# 2_Battery_Monitoring_And_Switches.net
KiCad netlist of a schematic drawn in Altium Designer
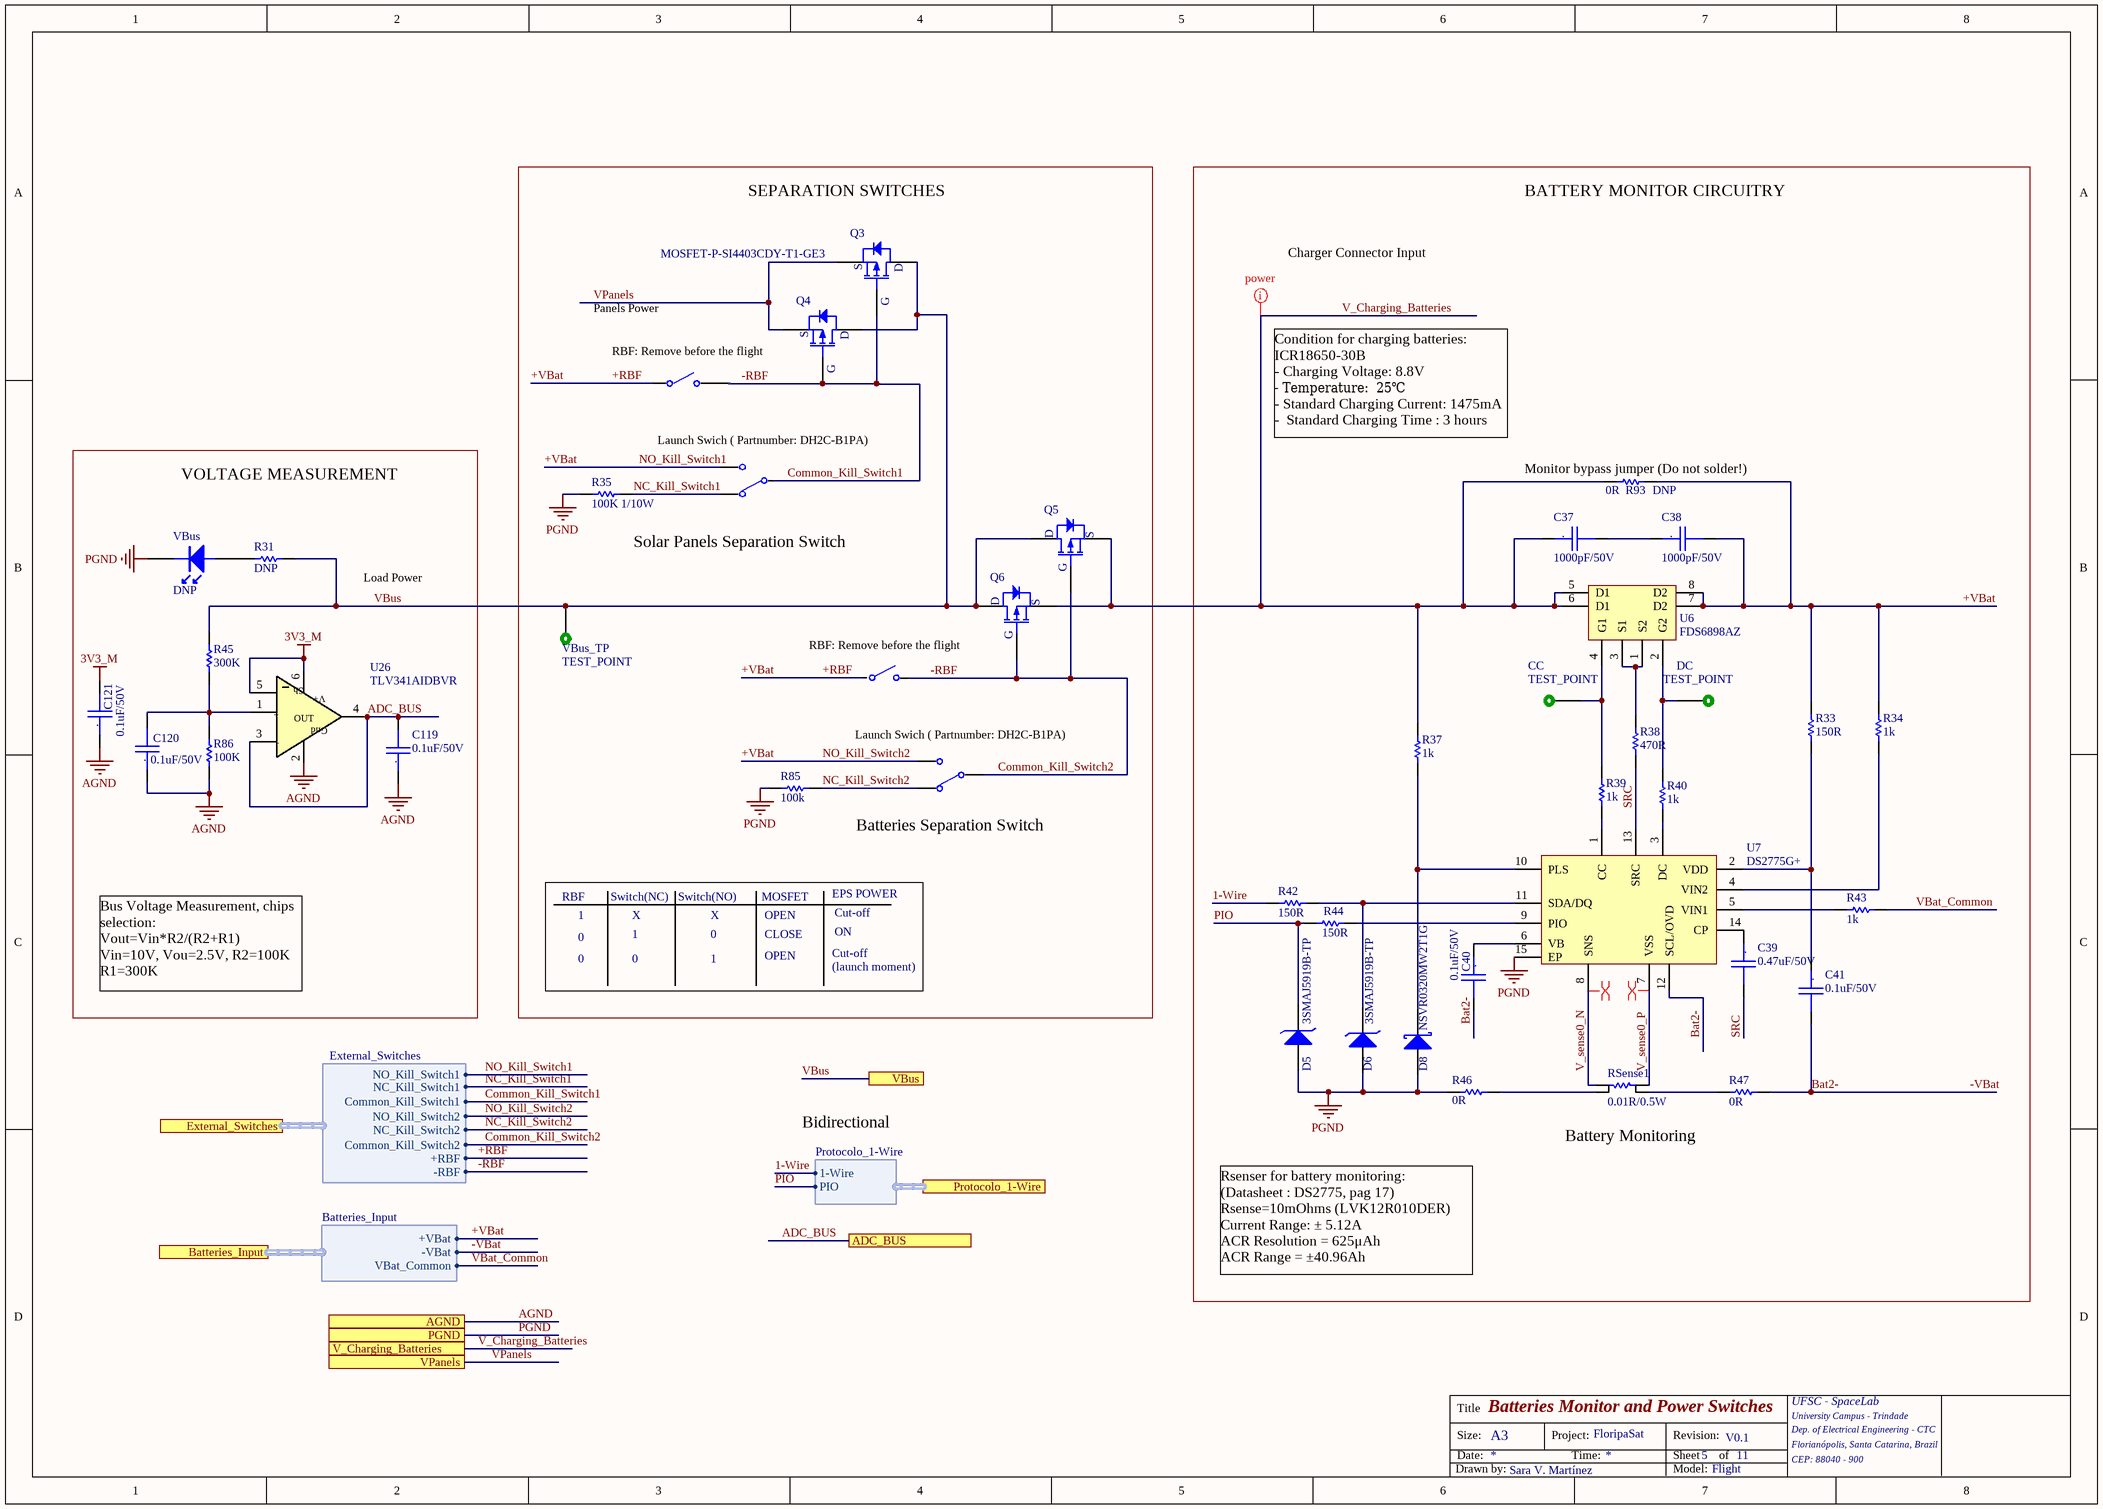
[diagram p0: 2_Battery_Monitoring_And_Switches.SchDoc]

(export (version "E")
  (design (tool "Eeschema 10.0.6"))
  (components
    (comp (ref "C37")
      (value "1000pF/50V")
      (footprint "CC0603")
      (description "CAP CER 1000pF 50V 10% X7R 0603")
      (fields (field (name "PARTNUMBER") "GRM188R71H102KA01D"))
      (libsource (lib "Floripasat_lib") (part "Cap_Cer_X7R_1000pF_50V_0603"))
    )
    (comp (ref "C38")
      (value "1000pF/50V")
      (footprint "CC0603")
      (description "CAP CER 1000pF 50V 10% X7R 0603")
      (fields (field (name "PARTNUMBER") "GRM188R71H102KA01D"))
      (libsource (lib "Floripasat_lib") (part "Cap_Cer_X7R_1000pF_50V_0603"))
    )
    (comp (ref "C39")
      (value "0.47uF/50V")
      (footprint "CC0603")
      (description "CAP CER 0.47UF 50V 10% X7R 0603")
      (fields (field (name "PARTNUMBER") "C1608X7R1H474K080AE"))
      (libsource (lib "FloripaSatSchlib") (part "Cap_Cer_X7R_0.47uF_50V_0603"))
    )
    (comp (ref "C40")
      (value "0.1uF/50V")
      (footprint "CC0603")
      (description "CAP CER 0.1UF 50V 10% X7R 0603")
      (fields (field (name "PARTNUMBER") "GRM188R71H104KA93D"))
      (libsource (lib "FloripaSatSchlib") (part "Cap_Cer_X7R_0.1uF_50V_0603"))
    )
    (comp (ref "C41")
      (value "0.1uF/50V")
      (footprint "CC0603")
      (description "CAP CER 0.1UF 50V 10% X7R 0603")
      (fields (field (name "PARTNUMBER") "GRM188R71H104KA93D"))
      (libsource (lib "FloripaSatSchlib") (part "Cap_Cer_X7R_0.1uF_50V_0603"))
    )
    (comp (ref "C119")
      (value "0.1uF/50V")
      (footprint "CC0603")
      (description "CAP CER 0.1UF 50V 10% X7R 0603")
      (fields (field (name "PARTNUMBER") "GRM188R71H104KA93D"))
      (libsource (lib "FloripaSatSchlib") (part "Cap_Cer_X7R_0.1uF_50V_0603"))
    )
    (comp (ref "C120")
      (value "0.1uF/50V")
      (footprint "CC0603")
      (description "CAP CER 0.1UF 50V 10% X7R 0603")
      (fields (field (name "PARTNUMBER") "GRM188R71H104KA93D"))
      (libsource (lib "FloripaSatSchlib") (part "Cap_Cer_X7R_0.1uF_50V_0603"))
    )
    (comp (ref "C121")
      (value "0.1uF/50V")
      (footprint "CC0603")
      (description "CAP CER 0.1UF 50V 10% X7R 0603")
      (fields (field (name "PARTNUMBER") "GRM188R71H104KA93D"))
      (libsource (lib "FloripaSatSchlib") (part "Cap_Cer_X7R_0.1uF_50V_0603"))
    )
    (comp (ref "CC")
      (value "TEST_POINT")
      (footprint "TEST_POINT")
      (description "Test point")
      (libsource (lib "Floripasat_lib") (part "TEST_POINT"))
    )
    (comp (ref "D5")
      (value "3SMAJ5919B-TP")
      (footprint "DO-214AC")
      (description "DIODE ZENER 5.6V 3W DO214AC")
      (libsource (lib "Floripasat_lib") (part "DIODE_ZENER_5.6V_3SMAJ5919B"))
    )
    (comp (ref "D6")
      (value "3SMAJ5919B-TP")
      (footprint "DO-214AC")
      (description "DIODE ZENER 5.6V 3W DO214AC")
      (libsource (lib "Floripasat_lib") (part "DIODE_ZENER_5.6V_3SMAJ5919B"))
    )
    (comp (ref "D8")
      (value "NSVR0320MW2T1G")
      (footprint "SOD323F")
      (description "DIODE SCHOTTKY 23V 1A SOD323F")
      (libsource (lib "FloripaSatSchlib") (part "DIODE_SCHOTTKY_23V_1A_NSVR0320MW2T1G"))
    )
    (comp (ref "DC")
      (value "TEST_POINT")
      (footprint "TEST_POINT")
      (description "Test point")
      (libsource (lib "Floripasat_lib") (part "TEST_POINT"))
    )
    (comp (ref "Q3")
      (value "MOSFET-P-SI4403CDY-T1-GE3")
      (footprint "SOIC8_Mosfet")
      (description "MOSFET 1.8V P-Channel 20 V, 0.0155 Ω typ., 13.4 A")
      (fields (field (name "PARTNUMBER") "SI4403CDY-T1-GE3") (field (name "PUBLISHER") "Altium Limited"))
      (libsource (lib "FloripaSatSchlib") (part "MOSFET-P- SI4403CDY-T1-GE3"))
    )
    (comp (ref "Q4")
      (value "MOSFET-P-SI4403CDY-T1-GE3")
      (footprint "SOIC8_Mosfet")
      (description "MOSFET 1.8V P-Channel 20 V, 0.0155 Ω typ., 13.4 A")
      (fields (field (name "PARTNUMBER") "SI4403CDY-T1-GE3") (field (name "PUBLISHER") "Altium Limited"))
      (libsource (lib "FloripaSatSchlib") (part "MOSFET-P- SI4403CDY-T1-GE3"))
    )
    (comp (ref "Q5")
      (value "MOSFET-P-SI4403CDY-T1-GE3")
      (footprint "SOIC8_Mosfet")
      (description "MOSFET 1.8V P-Channel 20 V, 0.0155 Ω typ., 13.4 A")
      (fields (field (name "PARTNUMBER") "SI4403CDY-T1-GE3") (field (name "PUBLISHER") "Altium Limited"))
      (libsource (lib "FloripaSatSchlib") (part "MOSFET-P- SI4403CDY-T1-GE3"))
    )
    (comp (ref "Q6")
      (value "MOSFET-P-SI4403CDY-T1-GE3")
      (footprint "SOIC8_Mosfet")
      (description "MOSFET 1.8V P-Channel 20 V, 0.0155 Ω typ., 13.4 A")
      (fields (field (name "PARTNUMBER") "SI4403CDY-T1-GE3") (field (name "PUBLISHER") "Altium Limited"))
      (libsource (lib "FloripaSatSchlib") (part "MOSFET-P- SI4403CDY-T1-GE3"))
    )
    (comp (ref "R31")
      (value "DNP")
      (footprint "0603")
      (description "RES 1.0K OHM 1/8W 1% 0603")
      (fields (field (name "PARTNUMBER") "MCT06030C1001FP500"))
      (libsource (lib "FloripaSatSchlib") (part "R1.0k_1%_1/8W_0603"))
    )
    (comp (ref "R33")
      (value "150R")
      (footprint "0603")
      (description "RES 150R OHM 1/8W 1% 0603")
      (fields (field (name "PARTNUMBER") "CRCW0603150RFKEA"))
      (libsource (lib "FloripaSatSchlib") (part "R150R_1%_1/8W_0603"))
    )
    (comp (ref "R34")
      (value "1k")
      (footprint "0603")
      (description "RES 1.0K OHM 1/8W 1% 0603")
      (fields (field (name "PARTNUMBER") "MCT06030C1001FP500"))
      (libsource (lib "FloripaSatSchlib") (part "R1.0k_1%_1/8W_0603"))
    )
    (comp (ref "R35")
      (value "100K 1/10W")
      (footprint "0805")
      (description "RES 100K OHM 1/10W 0.1% 0805")
      (fields (field (name "PARTNUMBER") "CPF-A-0805B100KE"))
      (libsource (lib "FloripaSatSchlib") (part "R100R_0.1%_1/10W_0805"))
    )
    (comp (ref "R37")
      (value "1k")
      (footprint "0603")
      (description "RES 1.0K OHM 1/8W 1% 0603")
      (fields (field (name "PARTNUMBER") "MCT06030C1001FP500"))
      (libsource (lib "FloripaSatSchlib") (part "R1.0k_1%_1/8W_0603"))
    )
    (comp (ref "R38")
      (value "470R")
      (footprint "0603")
      (description "RES 470R OHM 1/8W 1% 0603")
      (fields (field (name "PARTNUMBER") "MCT06030C4700FP500"))
      (libsource (lib "FloripaSatSchlib") (part "R470R_1%_1/8W_0603"))
    )
    (comp (ref "R39")
      (value "1k")
      (footprint "0603")
      (description "RES 1.0K OHM 1/8W 1% 0603")
      (fields (field (name "PARTNUMBER") "MCT06030C1001FP500"))
      (libsource (lib "FloripaSatSchlib") (part "R1.0k_1%_1/8W_0603"))
    )
    (comp (ref "R40")
      (value "1k")
      (footprint "0603")
      (description "RES 1.0K OHM 1/8W 1% 0603")
      (fields (field (name "PARTNUMBER") "MCT06030C1001FP500"))
      (libsource (lib "FloripaSatSchlib") (part "R1.0k_1%_1/8W_0603"))
    )
    (comp (ref "R42")
      (value "150R")
      (footprint "0603")
      (description "RES 150R OHM 1/8W 1% 0603")
      (fields (field (name "PARTNUMBER") "CRCW0603150RFKEA"))
      (libsource (lib "FloripaSatSchlib") (part "R150R_1%_1/8W_0603"))
    )
    (comp (ref "R43")
      (value "1k")
      (footprint "0603")
      (description "RES 1.0K OHM 1/8W 1% 0603")
      (fields (field (name "PARTNUMBER") "MCT06030C1001FP500"))
      (libsource (lib "FloripaSatSchlib") (part "R1.0k_1%_1/8W_0603"))
    )
    (comp (ref "R44")
      (value "150R")
      (footprint "0603")
      (description "RES 150R OHM 1/8W 1% 0603")
      (fields (field (name "PARTNUMBER") "CRCW0603150RFKEA"))
      (libsource (lib "FloripaSatSchlib") (part "R150R_1%_1/8W_0603"))
    )
    (comp (ref "R45")
      (value "300K")
      (footprint "0603")
      (description "RES 300K OHM 1/10W 0.1% 0603")
      (fields (field (name "PARTNUMBER") "RG1608P-304-B-T5"))
      (libsource (lib "FloripaSatSchlib") (part "R300K_0.1%_1/10W_0603"))
    )
    (comp (ref "R46")
      (value "0R")
      (footprint "1206")
      (description "RES 0.0 OHM 1/2W JUMP 1206")
      (fields (field (name "PARTNUMBER") "CRCW12060000Z0EAHP"))
      (libsource (lib "FloripaSatSchlib") (part "R0R_JUMPER_1/2W_1206"))
    )
    (comp (ref "R47")
      (value "0R")
      (footprint "1206")
      (description "RES 0.0 OHM 1/2W JUMP 1206")
      (fields (field (name "PARTNUMBER") "CRCW12060000Z0EAHP"))
      (libsource (lib "FloripaSatSchlib") (part "R0R_JUMPER_1/2W_1206"))
    )
    (comp (ref "R85")
      (value "100k")
      (footprint "0805")
      (description "RES 100k OHM 1/8W 1% 0805")
      (fields (field (name "PARTNUMBER") "CPF-A-0805B100KE"))
      (libsource (lib "FloripaSatSchlib") (part "R1.0k_1%_1/8W_0805"))
    )
    (comp (ref "R86")
      (value "100K")
      (footprint "0603")
      (description "RES 100K OHM 1/10W 1% 0603")
      (fields (field (name "PARTNUMBER") "CRCW0603100KFKEA"))
      (libsource (lib "FloripaSatSchlib") (part "R100K_1%_1/10W_0603"))
    )
    (comp (ref "R93")
      (value "0R")
      (footprint "1206")
      (description "RES 0.0 OHM 1/2W JUMP 1206")
      (fields (field (name "PARTNUMBER") "CRCW12060000Z0EAHP"))
      (libsource (lib "FloripaSatSchlib") (part "R0R_JUMPER_1/2W_1206"))
    )
    (comp (ref "RSense1")
      (value "0.01R/0.5W")
      (footprint "1206 - ohmite")
      (description "Current Sense Resistors - SMD 0.01ohm .5% 4 Terminal")
      (fields (field (name "PARTNUMBER") "LVK12R010DER"))
      (libsource (lib "FloripaSatSchlib") (part "R0.01R_0.5%_0.5W_1206_4_terminal"))
    )
    (comp (ref "U6")
      (value "FDS6898AZ")
      (footprint "SOIC8")
      (description "MOSFET 2N-CH 20V 9.4A 8SOIC")
      (libsource (lib "FloripaSatSchlib") (part "FDS6898AZ"))
    )
    (comp (ref "U7")
      (value "DS2775G+")
      (footprint "TDFN-14-EP_3x5")
      (description "IC FUEL GAUGE LI+ 2CELL 14-TDFN")
      (libsource (lib "FloripaSatSchlib") (part "DS2775G+"))
    )
    (comp (ref "U26")
      (value "TLV341AIDBVR")
      (footprint "SOT-23 6L")
      (libsource (lib "componentes_6_11") (part "TLV341AIDBVR"))
    )
    (comp (ref "VBus")
      (value "DNP")
      (footprint "0603-LED")
      (description "SMD Green LED")
      (fields (field (name "PARTNUMBER") "150060VS75000"))
      (libsource (lib "FloripaSatSchlib") (part "LED/G_0603"))
    )
    (comp (ref "VBus_TP")
      (value "TEST_POINT")
      (footprint "TEST_POINT")
      (description "Test point")
      (libsource (lib "Floripasat_lib") (part "TEST_POINT"))
    )
  )
  (nets
    (net (code "4") (name "/+RBF") (class "Default")
      (node (ref "C38") (pin "2") (pinfunction "2_2") (pintype "passive"))
      (node (ref "R33") (pin "1") (pinfunction "1_1") (pintype "passive"))
      (node (ref "R34") (pin "2") (pinfunction "2_2") (pintype "passive"))
      (node (ref "R93") (pin "2") (pinfunction "2_2") (pintype "passive"))
      (node (ref "U6") (pin "7") (pinfunction "D2_7") (pintype "passive"))
      (node (ref "U6") (pin "8") (pinfunction "D2_8") (pintype "passive"))
    )
    (net (code "5") (name "/-RBF") (class "Default")
      (node (ref "Q3") (pin "2") (pinfunction "G_2") (pintype "passive"))
      (node (ref "Q4") (pin "2") (pinfunction "G_2") (pintype "passive"))
      (node (ref "Q5") (pin "2") (pinfunction "G_2") (pintype "passive"))
      (node (ref "Q6") (pin "2") (pinfunction "G_2") (pintype "passive"))
    )
    (net (code "6") (name "/-VBat") (class "Default")
      (node (ref "C40") (pin "2") (pinfunction "2_2") (pintype "passive"))
      (node (ref "C41") (pin "2") (pinfunction "2_2") (pintype "passive"))
      (node (ref "R47") (pin "1") (pinfunction "1_1") (pintype "passive"))
      (node (ref "U7") (pin "12") (pinfunction "SCL/OVD_12") (pintype "passive"))
    )
    (net (code "7") (name "/1-Wire") (class "Default")
      (node (ref "R42") (pin "2") (pinfunction "2_2") (pintype "passive"))
    )
    (net (code "8") (name "/ADC_BUS") (class "Default")
      (node (ref "C119") (pin "2") (pinfunction "2_2") (pintype "passive"))
      (node (ref "U26") (pin "3") (pinfunction "-IN_3") (pintype "passive"))
      (node (ref "U26") (pin "4") (pinfunction "OUT_4") (pintype "passive"))
    )
    (net (code "9") (name "/NC_Kill_Switch1") (class "Default")
      (node (ref "R35") (pin "2") (pinfunction "2_2") (pintype "passive"))
    )
    (net (code "10") (name "/NC_Kill_Switch2") (class "Default")
      (node (ref "R85") (pin "2") (pinfunction "2_2") (pintype "passive"))
    )
    (net (code "11") (name "/PIO") (class "Default")
      (node (ref "D5") (pin "1") (pinfunction "K_1") (pintype "passive"))
      (node (ref "R44") (pin "2") (pinfunction "2_2") (pintype "passive"))
    )
    (net (code "12") (name "/SRC") (class "Default")
      (node (ref "C39") (pin "2") (pinfunction "2_2") (pintype "passive"))
      (node (ref "R38") (pin "1") (pinfunction "1_1") (pintype "passive"))
      (node (ref "U7") (pin "13") (pinfunction "SRC_13") (pintype "passive"))
    )
    (net (code "13") (name "/VBat_Common") (class "Default")
      (node (ref "R43") (pin "1") (pinfunction "1_1") (pintype "passive"))
    )
    (net (code "14") (name "/VBus") (class "Default")
      (node (ref "Q3") (pin "3") (pinfunction "D_3") (pintype "passive"))
      (node (ref "Q4") (pin "3") (pinfunction "D_3") (pintype "passive"))
      (node (ref "Q5") (pin "3") (pinfunction "D_3") (pintype "passive"))
      (node (ref "Q6") (pin "3") (pinfunction "D_3") (pintype "passive"))
      (node (ref "R31") (pin "1") (pinfunction "1_1") (pintype "passive"))
      (node (ref "R45") (pin "2") (pinfunction "2_2") (pintype "passive"))
      (node (ref "VBus_TP") (pin "1") (pinfunction "1_1") (pintype "passive"))
    )
    (net (code "15") (name "/VPanels") (class "Default")
      (node (ref "Q3") (pin "1") (pinfunction "S_1") (pintype "passive"))
      (node (ref "Q4") (pin "1") (pinfunction "S_1") (pintype "passive"))
    )
    (net (code "16") (name "/V_Charging_Batteries") (class "Default")
      (node (ref "C37") (pin "1") (pinfunction "1_1") (pintype "passive"))
      (node (ref "Q5") (pin "1") (pinfunction "S_1") (pintype "passive"))
      (node (ref "Q6") (pin "1") (pinfunction "S_1") (pintype "passive"))
      (node (ref "R37") (pin "2") (pinfunction "2_2") (pintype "passive"))
      (node (ref "R93") (pin "1") (pinfunction "1_1") (pintype "passive"))
      (node (ref "U6") (pin "5") (pinfunction "D1_5") (pintype "passive"))
      (node (ref "U6") (pin "6") (pinfunction "D1_6") (pintype "passive"))
    )
    (net (code "17") (name "/V_sense0_N") (class "Default")
      (node (ref "RSense1") (pin "2") (pinfunction "2_2") (pintype "passive"))
      (node (ref "U7") (pin "8") (pinfunction "SNS_8") (pintype "passive"))
    )
    (net (code "18") (name "/V_sense0_P") (class "Default")
      (node (ref "RSense1") (pin "1") (pinfunction "1_1") (pintype "passive"))
      (node (ref "U7") (pin "7") (pinfunction "VSS_7") (pintype "passive"))
    )
    (net (code "22") (name "3V3_M") (class "Default")
      (node (ref "C121") (pin "2") (pinfunction "2_2") (pintype "passive"))
      (node (ref "U26") (pin "5") (pinfunction "EN_5") (pintype "passive"))
      (node (ref "U26") (pin "6") (pinfunction "V+_6") (pintype "passive"))
    )
    (net (code "23") (name "AGND") (class "Default")
      (node (ref "C119") (pin "1") (pinfunction "1_1") (pintype "passive"))
      (node (ref "C120") (pin "1") (pinfunction "1_1") (pintype "passive"))
      (node (ref "C121") (pin "1") (pinfunction "1_1") (pintype "passive"))
      (node (ref "R86") (pin "1") (pinfunction "1_1") (pintype "passive"))
      (node (ref "U26") (pin "2") (pinfunction "Gnd_2") (pintype "passive"))
    )
    (net (code "24") (name "Net-(C37-Pad2)") (class "Default")
      (node (ref "C37") (pin "2") (pinfunction "2_2") (pintype "passive"))
      (node (ref "C38") (pin "1") (pinfunction "1_1") (pintype "passive"))
    )
    (net (code "25") (name "Net-(D6-K)") (class "Default")
      (node (ref "D6") (pin "1") (pinfunction "K_1") (pintype "passive"))
      (node (ref "R42") (pin "1") (pinfunction "1_1") (pintype "passive"))
      (node (ref "U7") (pin "11") (pinfunction "SDA/DQ_11") (pintype "passive"))
    )
    (net (code "26") (name "Net-(D8-K)") (class "Default")
      (node (ref "D8") (pin "1") (pinfunction "K_1") (pintype "passive"))
      (node (ref "R37") (pin "1") (pinfunction "1_1") (pintype "passive"))
      (node (ref "U7") (pin "10") (pinfunction "PLS_10") (pintype "passive"))
    )
    (net (code "27") (name "Net-(R46-Pad1)") (class "Default")
      (node (ref "R46") (pin "1") (pinfunction "1_1") (pintype "passive"))
      (node (ref "RSense1") (pin "4") (pinfunction "4_4") (pintype "passive"))
    )
    (net (code "28") (name "Net-(R47-Pad2)") (class "Default")
      (node (ref "R47") (pin "2") (pinfunction "2_2") (pintype "passive"))
      (node (ref "RSense1") (pin "3") (pinfunction "3_3") (pintype "passive"))
    )
    (net (code "29") (name "Net-(U6-G1)") (class "Default")
      (node (ref "CC") (pin "1") (pinfunction "1_1") (pintype "passive"))
      (node (ref "R39") (pin "2") (pinfunction "2_2") (pintype "passive"))
      (node (ref "U6") (pin "4") (pinfunction "G1_4") (pintype "passive"))
    )
    (net (code "30") (name "Net-(U6-G2)") (class "Default")
      (node (ref "DC") (pin "1") (pinfunction "1_1") (pintype "passive"))
      (node (ref "R40") (pin "2") (pinfunction "2_2") (pintype "passive"))
      (node (ref "U6") (pin "2") (pinfunction "G2_2") (pintype "passive"))
    )
    (net (code "31") (name "Net-(U6-S1)") (class "Default")
      (node (ref "R38") (pin "2") (pinfunction "2_2") (pintype "passive"))
      (node (ref "U6") (pin "1") (pinfunction "S2_1") (pintype "passive"))
      (node (ref "U6") (pin "3") (pinfunction "S1_3") (pintype "passive"))
    )
    (net (code "32") (name "Net-(U7-CC)") (class "Default")
      (node (ref "R39") (pin "1") (pinfunction "1_1") (pintype "passive"))
      (node (ref "U7") (pin "1") (pinfunction "CC_1") (pintype "passive"))
    )
    (net (code "33") (name "Net-(U7-CP)") (class "Default")
      (node (ref "C39") (pin "1") (pinfunction "1_1") (pintype "passive"))
      (node (ref "U7") (pin "14") (pinfunction "CP_14") (pintype "passive"))
    )
    (net (code "34") (name "Net-(U7-DC)") (class "Default")
      (node (ref "R40") (pin "1") (pinfunction "1_1") (pintype "passive"))
      (node (ref "U7") (pin "3") (pinfunction "DC_3") (pintype "passive"))
    )
    (net (code "35") (name "Net-(U7-PIO)") (class "Default")
      (node (ref "R44") (pin "1") (pinfunction "1_1") (pintype "passive"))
      (node (ref "U7") (pin "9") (pinfunction "PIO_9") (pintype "passive"))
    )
    (net (code "36") (name "Net-(U7-VB)") (class "Default")
      (node (ref "C40") (pin "1") (pinfunction "1_1") (pintype "passive"))
      (node (ref "U7") (pin "6") (pinfunction "VB_6") (pintype "passive"))
    )
    (net (code "37") (name "Net-(U7-VDD)") (class "Default")
      (node (ref "C41") (pin "1") (pinfunction "1_1") (pintype "passive"))
      (node (ref "R33") (pin "2") (pinfunction "2_2") (pintype "passive"))
      (node (ref "U7") (pin "2") (pinfunction "VDD_2") (pintype "passive"))
    )
    (net (code "38") (name "Net-(U7-VIN1)") (class "Default")
      (node (ref "R43") (pin "2") (pinfunction "2_2") (pintype "passive"))
      (node (ref "U7") (pin "5") (pinfunction "VIN1_5") (pintype "passive"))
    )
    (net (code "39") (name "Net-(U7-VIN2)") (class "Default")
      (node (ref "R34") (pin "1") (pinfunction "1_1") (pintype "passive"))
      (node (ref "U7") (pin "4") (pinfunction "VIN2_4") (pintype "passive"))
    )
    (net (code "40") (name "Net-(U26-+IN)") (class "Default")
      (node (ref "C120") (pin "2") (pinfunction "2_2") (pintype "passive"))
      (node (ref "R45") (pin "1") (pinfunction "1_1") (pintype "passive"))
      (node (ref "R86") (pin "2") (pinfunction "2_2") (pintype "passive"))
      (node (ref "U26") (pin "1") (pinfunction "+IN_1") (pintype "passive"))
    )
    (net (code "41") (name "Net-(VBus-A)") (class "Default")
      (node (ref "R31") (pin "2") (pinfunction "2_2") (pintype "passive"))
      (node (ref "VBus") (pin "1") (pinfunction "A_1") (pintype "passive"))
    )
    (net (code "42") (name "PGND") (class "Default")
      (node (ref "D5") (pin "2") (pinfunction "A_2") (pintype "passive"))
      (node (ref "D6") (pin "2") (pinfunction "A_2") (pintype "passive"))
      (node (ref "D8") (pin "2") (pinfunction "A_2") (pintype "passive"))
      (node (ref "R35") (pin "1") (pinfunction "1_1") (pintype "passive"))
      (node (ref "R46") (pin "2") (pinfunction "2_2") (pintype "passive"))
      (node (ref "R85") (pin "1") (pinfunction "1_1") (pintype "passive"))
      (node (ref "U7") (pin "15") (pinfunction "EP_15") (pintype "passive"))
      (node (ref "VBus") (pin "2") (pinfunction "K_2") (pintype "passive"))
    )
  )
)
